# HRT_23D_EBS_Non1_1.net
KiCad netlist of a schematic drawn in Altium Designer
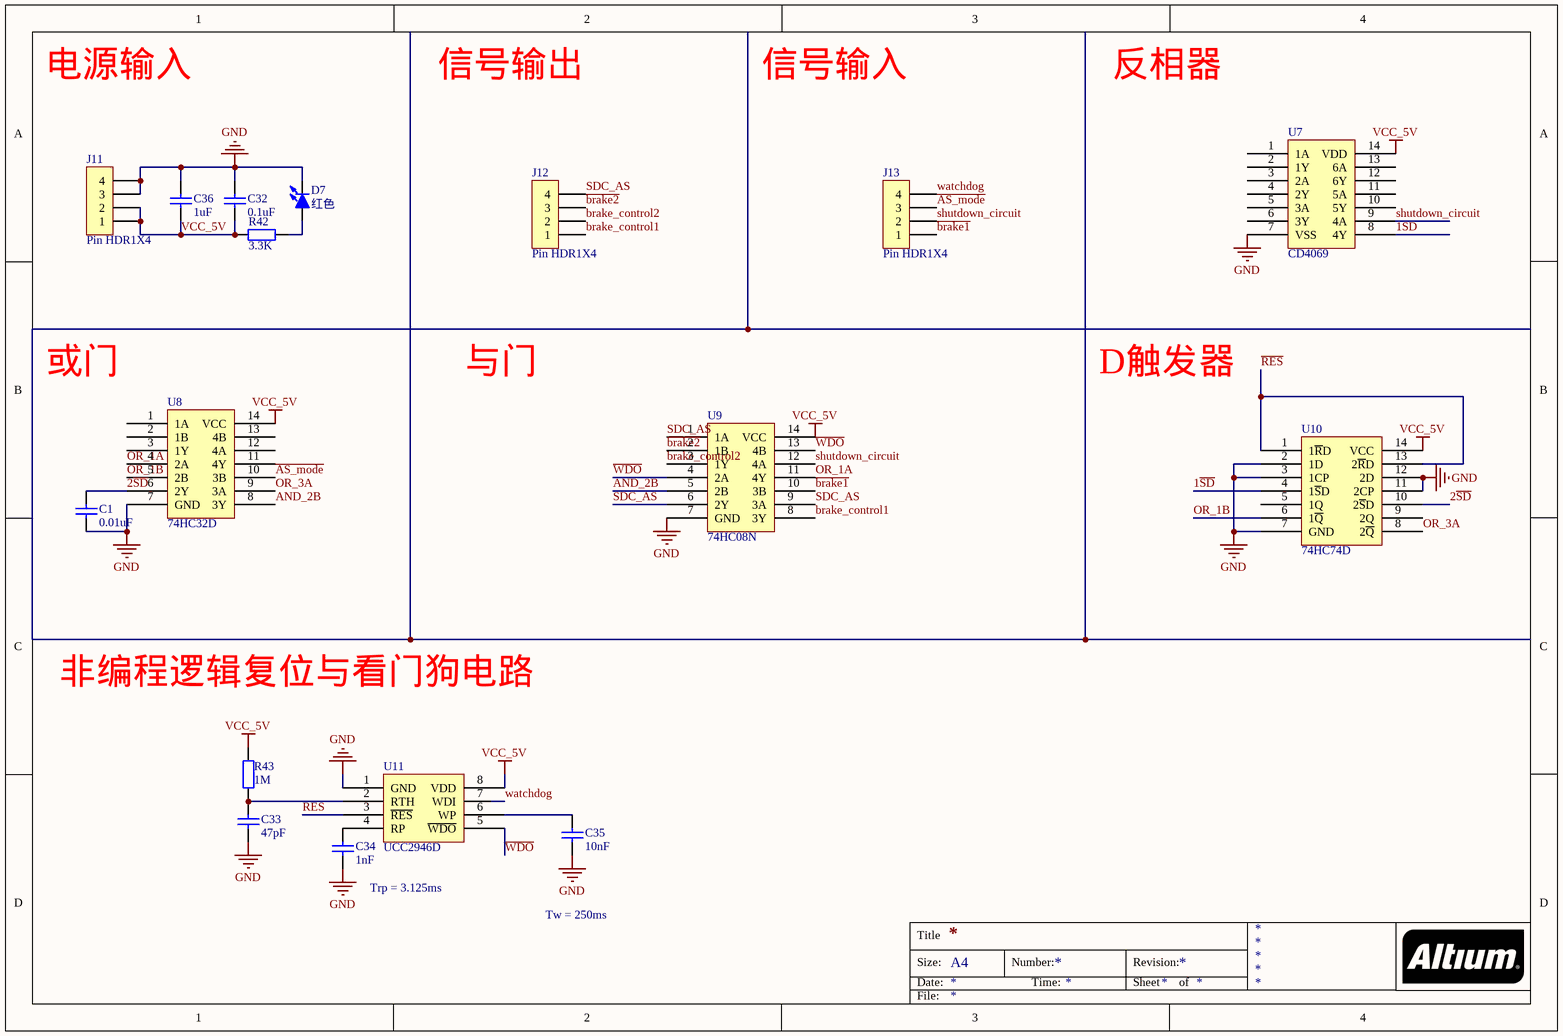
[diagram p0: HRT_23D_EBS_Non1.1.SchDoc]

(export (version "E")
  (design (tool "Eeschema 10.0.6"))
  (components
    (comp (ref "C1")
      (value "0.01uF")
      (footprint "C 0805_M")
      (description "无极性贴片电容")
      (libsource (lib "mainlib") (part "C"))
    )
    (comp (ref "C32")
      (value "0.1uF")
      (footprint "C 0805_M")
      (description "无极性贴片电容")
      (libsource (lib "mainlib") (part "C"))
    )
    (comp (ref "C33")
      (value "47pF")
      (footprint "C 0805_M")
      (description "无极性贴片电容")
      (libsource (lib "mainlib") (part "C"))
    )
    (comp (ref "C34")
      (value "1nF")
      (footprint "C 0805_M")
      (description "无极性贴片电容")
      (libsource (lib "mainlib") (part "C"))
    )
    (comp (ref "C35")
      (value "10nF")
      (footprint "C 0805_M")
      (description "无极性贴片电容")
      (libsource (lib "mainlib") (part "C"))
    )
    (comp (ref "C36")
      (value "1uF")
      (footprint "C 0805_M")
      (description "无极性贴片电容")
      (libsource (lib "mainlib") (part "C"))
    )
    (comp (ref "D7")
      (value "红色")
      (footprint "LED 0805G")
      (description "贴片LED")
      (fields (field (name "版权归属") "源创客"))
      (libsource (lib "mainlib") (part "LED-SMD"))
    )
    (comp (ref "J11")
      (value "Pin HDR1X4")
      (footprint "Pin HDR1X4/2.54mm-S")
      (libsource (lib "mainlib") (part "Pin HDR1X4"))
    )
    (comp (ref "J12")
      (value "Pin HDR1X4")
      (footprint "Pin HDR1X4/2.54mm-S")
      (libsource (lib "mainlib") (part "Pin HDR1X4"))
    )
    (comp (ref "J13")
      (value "Pin HDR1X4")
      (footprint "Pin HDR1X4/2.54mm-S")
      (libsource (lib "mainlib") (part "Pin HDR1X4"))
    )
    (comp (ref "R42")
      (value "3.3K")
      (footprint "0805R")
      (description "贴片电阻")
      (libsource (lib "mainlib") (part "RES"))
    )
    (comp (ref "R43")
      (value "1M")
      (footprint "0805R")
      (description "贴片电阻")
      (libsource (lib "") (part "RES_1"))
    )
    (comp (ref "U7")
      (value "CD4069")
      (footprint "SOP14")
      (description "反相器")
      (libsource (lib "digital_chips") (part "CD4069"))
    )
    (comp (ref "U8")
      (value "74HC32D")
      (footprint "SOP14")
      (description "2输入或门")
      (libsource (lib "digital_chips") (part "74HC32D"))
    )
    (comp (ref "U9")
      (value "74HC08N")
      (footprint "SOP14")
      (description "2输入与门")
      (libsource (lib "digital_chips") (part "74HC08N"))
    )
    (comp (ref "U10")
      (value "74HC74D")
      (footprint "SOP14")
      (description "D触发器")
      (libsource (lib "digital_chips") (part "74HC74D"))
    )
    (comp (ref "U11")
      (value "UCC2946D")
      (footprint "SOP8")
      (description "复位监控芯片")
      (libsource (lib "digital_chips") (part "UCC2946D"))
    )
  )
  (nets
    (net (code "1") (name "/1~{SD}") (class "Default")
      (node (ref "U10") (pin "4") (pinfunction "1~{S}D_4") (pintype "passive"))
      (node (ref "U7") (pin "8") (pinfunction "4Y_8") (pintype "passive"))
    )
    (net (code "2") (name "/2~{SD}") (class "Default")
      (node (ref "C1") (pin "2") (pinfunction "2_2") (pintype "passive"))
      (node (ref "U10") (pin "10") (pinfunction "2~{S}D_10") (pintype "passive"))
      (node (ref "U8") (pin "6") (pinfunction "2Y_6") (pintype "passive"))
    )
    (net (code "3") (name "/AND_2B") (class "Default")
      (node (ref "U8") (pin "8") (pinfunction "3Y_8") (pintype "passive"))
      (node (ref "U9") (pin "5") (pinfunction "2B_5") (pintype "passive"))
    )
    (net (code "4") (name "/OR_1A") (class "Default")
      (node (ref "U8") (pin "4") (pinfunction "2A_4") (pintype "passive"))
      (node (ref "U9") (pin "11") (pinfunction "4Y_11") (pintype "passive"))
    )
    (net (code "5") (name "/OR_1B") (class "Default")
      (node (ref "U10") (pin "6") (pinfunction "1~{Q}_6") (pintype "passive"))
      (node (ref "U8") (pin "5") (pinfunction "2B_5") (pintype "passive"))
    )
    (net (code "6") (name "/OR_3A") (class "Default")
      (node (ref "U10") (pin "8") (pinfunction "2~{Q}_8") (pintype "passive"))
      (node (ref "U8") (pin "9") (pinfunction "3A_9") (pintype "passive"))
    )
    (net (code "7") (name "/SDC_AS") (class "Default")
      (node (ref "J12") (pin "4") (pinfunction "4_4") (pintype "passive"))
      (node (ref "U9") (pin "1") (pinfunction "1A_1") (pintype "passive"))
      (node (ref "U9") (pin "6") (pinfunction "2Y_6") (pintype "passive"))
      (node (ref "U9") (pin "9") (pinfunction "3A_9") (pintype "passive"))
    )
    (net (code "8") (name "/brake_control1") (class "Default")
      (node (ref "J12") (pin "1") (pinfunction "1_1") (pintype "passive"))
      (node (ref "U9") (pin "8") (pinfunction "3Y_8") (pintype "passive"))
    )
    (net (code "9") (name "/brake_control2") (class "Default")
      (node (ref "J12") (pin "2") (pinfunction "2_2") (pintype "passive"))
      (node (ref "U9") (pin "3") (pinfunction "1Y_3") (pintype "passive"))
    )
    (net (code "10") (name "/shutdown_circuit") (class "Default")
      (node (ref "J13") (pin "2") (pinfunction "2_2") (pintype "passive"))
      (node (ref "U7") (pin "9") (pinfunction "4A_9") (pintype "passive"))
      (node (ref "U9") (pin "12") (pinfunction "4A_12") (pintype "passive"))
    )
    (net (code "11") (name "/watchdog") (class "Default")
      (node (ref "J13") (pin "4") (pinfunction "4_4") (pintype "passive"))
      (node (ref "U11") (pin "7") (pinfunction "WDI_7") (pintype "passive"))
    )
    (net (code "12") (name "/~{AS_mode}") (class "Default")
      (node (ref "J13") (pin "3") (pinfunction "3_3") (pintype "passive"))
      (node (ref "U8") (pin "10") (pinfunction "3B_10") (pintype "passive"))
    )
    (net (code "13") (name "/~{RES}") (class "Default")
      (node (ref "U10") (pin "1") (pinfunction "1~{R}D_1") (pintype "passive"))
      (node (ref "U10") (pin "13") (pinfunction "2~{R}D_13") (pintype "passive"))
      (node (ref "U11") (pin "3") (pinfunction "~{RES}_3") (pintype "passive"))
    )
    (net (code "14") (name "/~{WDO}") (class "Default")
      (node (ref "U11") (pin "5") (pinfunction "~{WDO}_5") (pintype "passive"))
      (node (ref "U9") (pin "13") (pinfunction "4B_13") (pintype "passive"))
      (node (ref "U9") (pin "4") (pinfunction "2A_4") (pintype "passive"))
    )
    (net (code "15") (name "/~{brake1}") (class "Default")
      (node (ref "J13") (pin "1") (pinfunction "1_1") (pintype "passive"))
      (node (ref "U9") (pin "10") (pinfunction "3B_10") (pintype "passive"))
    )
    (net (code "16") (name "/~{brake2}") (class "Default")
      (node (ref "J12") (pin "3") (pinfunction "3_3") (pintype "passive"))
      (node (ref "U9") (pin "2") (pinfunction "1B_2") (pintype "passive"))
    )
    (net (code "17") (name "GND") (class "Default")
      (node (ref "C1") (pin "1") (pinfunction "1_1") (pintype "passive"))
      (node (ref "C32") (pin "2") (pinfunction "2_2") (pintype "passive"))
      (node (ref "C33") (pin "1") (pinfunction "1_1") (pintype "passive"))
      (node (ref "C34") (pin "1") (pinfunction "1_1") (pintype "passive"))
      (node (ref "C35") (pin "1") (pinfunction "1_1") (pintype "passive"))
      (node (ref "C36") (pin "2") (pinfunction "2_2") (pintype "passive"))
      (node (ref "D7") (pin "2") (pinfunction "K_2") (pintype "passive"))
      (node (ref "J11") (pin "3") (pinfunction "3_3") (pintype "passive"))
      (node (ref "J11") (pin "4") (pinfunction "4_4") (pintype "passive"))
      (node (ref "U10") (pin "11") (pinfunction "2CP_11") (pintype "passive"))
      (node (ref "U10") (pin "12") (pinfunction "2D_12") (pintype "passive"))
      (node (ref "U10") (pin "2") (pinfunction "1D_2") (pintype "passive"))
      (node (ref "U10") (pin "3") (pinfunction "1CP_3") (pintype "passive"))
      (node (ref "U10") (pin "7") (pinfunction "GND_7") (pintype "passive"))
      (node (ref "U11") (pin "1") (pinfunction "GND_1") (pintype "passive"))
      (node (ref "U7") (pin "7") (pinfunction "VSS_7") (pintype "passive"))
      (node (ref "U8") (pin "7") (pinfunction "GND_7") (pintype "passive"))
      (node (ref "U9") (pin "7") (pinfunction "GND_7") (pintype "passive"))
    )
    (net (code "18") (name "Net-(D7-A)") (class "Default")
      (node (ref "D7") (pin "1") (pinfunction "A_1") (pintype "passive"))
      (node (ref "R42") (pin "2") (pinfunction "2_2") (pintype "passive"))
    )
    (net (code "19") (name "Net-(U11-RP)") (class "Default")
      (node (ref "C34") (pin "2") (pinfunction "2_2") (pintype "passive"))
      (node (ref "U11") (pin "4") (pinfunction "RP_4") (pintype "passive"))
    )
    (net (code "20") (name "Net-(U11-RTH)") (class "Default")
      (node (ref "C33") (pin "2") (pinfunction "2_2") (pintype "passive"))
      (node (ref "R43") (pin "1") (pinfunction "1_1") (pintype "passive"))
      (node (ref "U11") (pin "2") (pinfunction "RTH_2") (pintype "passive"))
    )
    (net (code "21") (name "Net-(U11-WP)") (class "Default")
      (node (ref "C35") (pin "2") (pinfunction "2_2") (pintype "passive"))
      (node (ref "U11") (pin "6") (pinfunction "WP_6") (pintype "passive"))
    )
    (net (code "22") (name "VCC_5V") (class "Default")
      (node (ref "C32") (pin "1") (pinfunction "1_1") (pintype "passive"))
      (node (ref "C36") (pin "1") (pinfunction "1_1") (pintype "passive"))
      (node (ref "J11") (pin "1") (pinfunction "1_1") (pintype "passive"))
      (node (ref "J11") (pin "2") (pinfunction "2_2") (pintype "passive"))
      (node (ref "R42") (pin "1") (pinfunction "1_1") (pintype "passive"))
      (node (ref "R43") (pin "2") (pinfunction "2_2") (pintype "passive"))
      (node (ref "U10") (pin "14") (pinfunction "VCC_14") (pintype "passive"))
      (node (ref "U11") (pin "8") (pinfunction "VDD_8") (pintype "passive"))
      (node (ref "U7") (pin "14") (pinfunction "VDD_14") (pintype "passive"))
      (node (ref "U8") (pin "14") (pinfunction "VCC_14") (pintype "passive"))
      (node (ref "U9") (pin "14") (pinfunction "VCC_14") (pintype "passive"))
    )
    (net (code "23") (name "unconnected-(U7-1A-Pad1)") (class "Default")
      (node (ref "U7") (pin "1") (pinfunction "1A_1") (pintype "passive"))
    )
    (net (code "24") (name "unconnected-(U7-1Y-Pad2)") (class "Default")
      (node (ref "U7") (pin "2") (pinfunction "1Y_2") (pintype "passive"))
    )
    (net (code "25") (name "unconnected-(U7-2A-Pad3)") (class "Default")
      (node (ref "U7") (pin "3") (pinfunction "2A_3") (pintype "passive"))
    )
    (net (code "26") (name "unconnected-(U7-2Y-Pad4)") (class "Default")
      (node (ref "U7") (pin "4") (pinfunction "2Y_4") (pintype "passive"))
    )
    (net (code "27") (name "unconnected-(U7-3A-Pad5)") (class "Default")
      (node (ref "U7") (pin "5") (pinfunction "3A_5") (pintype "passive"))
    )
    (net (code "28") (name "unconnected-(U7-3Y-Pad6)") (class "Default")
      (node (ref "U7") (pin "6") (pinfunction "3Y_6") (pintype "passive"))
    )
    (net (code "29") (name "unconnected-(U7-5A-Pad11)") (class "Default")
      (node (ref "U7") (pin "11") (pinfunction "5A_11") (pintype "passive"))
    )
    (net (code "30") (name "unconnected-(U7-5Y-Pad10)") (class "Default")
      (node (ref "U7") (pin "10") (pinfunction "5Y_10") (pintype "passive"))
    )
    (net (code "31") (name "unconnected-(U7-6A-Pad13)") (class "Default")
      (node (ref "U7") (pin "13") (pinfunction "6A_13") (pintype "passive"))
    )
    (net (code "32") (name "unconnected-(U7-6Y-Pad12)") (class "Default")
      (node (ref "U7") (pin "12") (pinfunction "6Y_12") (pintype "passive"))
    )
    (net (code "33") (name "unconnected-(U8-1A-Pad1)") (class "Default")
      (node (ref "U8") (pin "1") (pinfunction "1A_1") (pintype "passive"))
    )
    (net (code "34") (name "unconnected-(U8-1B-Pad2)") (class "Default")
      (node (ref "U8") (pin "2") (pinfunction "1B_2") (pintype "passive"))
    )
    (net (code "35") (name "unconnected-(U8-1Y-Pad3)") (class "Default")
      (node (ref "U8") (pin "3") (pinfunction "1Y_3") (pintype "passive"))
    )
    (net (code "36") (name "unconnected-(U8-4A-Pad12)") (class "Default")
      (node (ref "U8") (pin "12") (pinfunction "4A_12") (pintype "passive"))
    )
    (net (code "37") (name "unconnected-(U8-4B-Pad13)") (class "Default")
      (node (ref "U8") (pin "13") (pinfunction "4B_13") (pintype "passive"))
    )
    (net (code "38") (name "unconnected-(U8-4Y-Pad11)") (class "Default")
      (node (ref "U8") (pin "11") (pinfunction "4Y_11") (pintype "passive"))
    )
    (net (code "39") (name "unconnected-(U10-1Q-Pad5)") (class "Default")
      (node (ref "U10") (pin "5") (pinfunction "1Q_5") (pintype "passive"))
    )
    (net (code "40") (name "unconnected-(U10-2Q-Pad9)") (class "Default")
      (node (ref "U10") (pin "9") (pinfunction "2Q_9") (pintype "passive"))
    )
  )
)
